# Relay_Control.net
KiCad netlist of a schematic drawn in Altium Designer
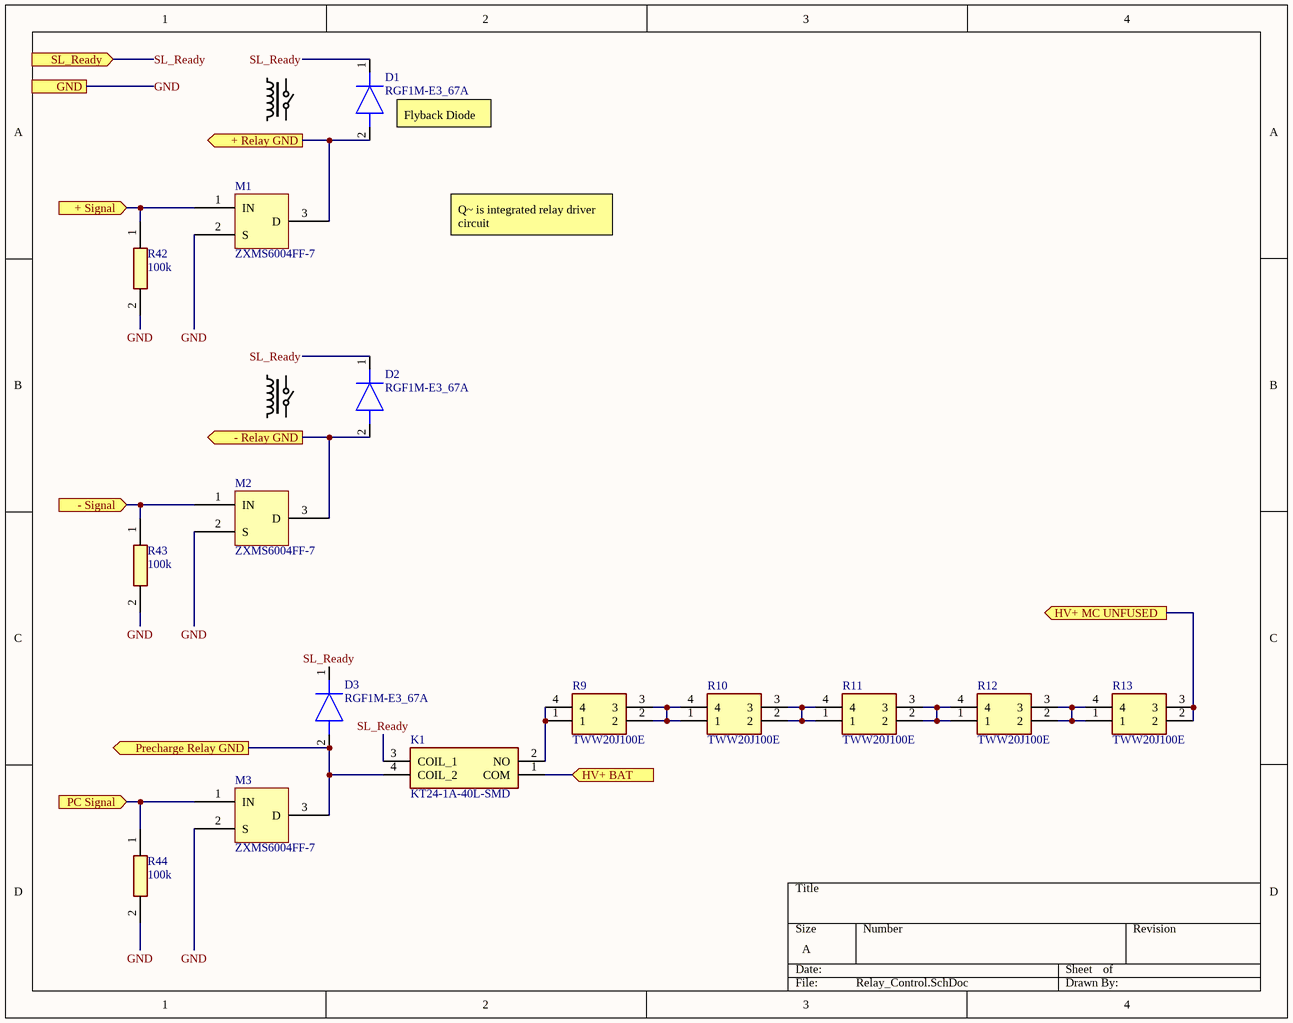
[diagram p0: Relay_Control.SchDoc]

(export (version "E")
  (design (tool "Eeschema 10.0.6"))
  (components
    (comp (ref "D1")
      (value "RGF1M-E3_67A")
      (footprint "SamacSys:DIOM5426X300N")
      (description "Diode")
      (fields
        (field (name "MANUFACTURER_PART_NUMBER") "RGF1M-E3/67A")
        (field (name "MOUSER PART NUMBER") "625-RGF1M-E3")
      )
      (libsource (lib "SamacSys") (part "RGF1M-E3_67A"))
    )
    (comp (ref "D2")
      (value "RGF1M-E3_67A")
      (footprint "SamacSys:DIOM5426X300N")
      (description "Diode")
      (fields
        (field (name "MANUFACTURER_PART_NUMBER") "RGF1M-E3/67A")
        (field (name "MOUSER PART NUMBER") "625-RGF1M-E3")
      )
      (libsource (lib "SamacSys") (part "RGF1M-E3_67A"))
    )
    (comp (ref "D3")
      (value "RGF1M-E3_67A")
      (footprint "SamacSys:DIOM5426X300N")
      (description "Diode")
      (fields
        (field (name "MANUFACTURER_PART_NUMBER") "RGF1M-E3/67A")
        (field (name "MOUSER PART NUMBER") "625-RGF1M-E3")
      )
      (libsource (lib "SamacSys") (part "RGF1M-E3_67A"))
    )
    (comp (ref "K1")
      (value "KT24-1A-40L-SMD")
      (footprint "SamacSys:KT241A40LSMD")
      (description "Relay or Contactor")
      (fields (field (name "MOUSER PART NUMBER") "876-KT24-1A-40L-SMD"))
      (libsource (lib "*") (part "KT24-1A-40L-SMD"))
    )
    (comp (ref "M1")
      (value "ZXMS6004FF-7")
      (footprint "SamacSys:SOT95P240X100-3N")
      (libsource (lib "SamacSys") (part "ZXMS6004FF-7"))
    )
    (comp (ref "M2")
      (value "ZXMS6004FF-7")
      (footprint "SamacSys:SOT95P240X100-3N")
      (libsource (lib "SamacSys") (part "ZXMS6004FF-7"))
    )
    (comp (ref "M3")
      (value "ZXMS6004FF-7")
      (footprint "SamacSys:SOT95P240X100-3N")
      (libsource (lib "SamacSys") (part "ZXMS6004FF-7"))
    )
    (comp (ref "R9")
      (value "TWW20J100E")
      (footprint "SamacSys:TWW20J100E")
      (description "Resistor")
      (fields (field (name "MOUSER PART NUMBER") "588-TWW20J100E"))
      (libsource (lib "*") (part "TWW20J100E"))
    )
    (comp (ref "R10")
      (value "TWW20J100E")
      (footprint "SamacSys:TWW20J100E")
      (description "Resistor")
      (fields (field (name "MOUSER PART NUMBER") "588-TWW20J100E"))
      (libsource (lib "*") (part "TWW20J100E"))
    )
    (comp (ref "R11")
      (value "TWW20J100E")
      (footprint "SamacSys:TWW20J100E")
      (description "Resistor")
      (fields (field (name "MOUSER PART NUMBER") "588-TWW20J100E"))
      (libsource (lib "*") (part "TWW20J100E"))
    )
    (comp (ref "R12")
      (value "TWW20J100E")
      (footprint "SamacSys:TWW20J100E")
      (description "Resistor")
      (fields (field (name "MOUSER PART NUMBER") "588-TWW20J100E"))
      (libsource (lib "*") (part "TWW20J100E"))
    )
    (comp (ref "R13")
      (value "TWW20J100E")
      (footprint "SamacSys:TWW20J100E")
      (description "Resistor")
      (fields (field (name "MOUSER PART NUMBER") "588-TWW20J100E"))
      (libsource (lib "*") (part "TWW20J100E"))
    )
    (comp (ref "R42")
      (value "100k")
      (footprint "SamacSys:RESC3216X65N")
      (description "Resistor")
      (fields (field (name "MANUFACTURER_PART_NUMBER") "MCA1206ME1003BP500"))
      (libsource (lib "*") (part "MCA1206ME1003BP500"))
    )
    (comp (ref "R43")
      (value "100k")
      (footprint "SamacSys:RESC3216X65N")
      (description "Resistor")
      (fields (field (name "MANUFACTURER_PART_NUMBER") "MCA1206ME1003BP500"))
      (libsource (lib "*") (part "MCA1206ME1003BP500"))
    )
    (comp (ref "R44")
      (value "100k")
      (footprint "SamacSys:RESC3216X65N")
      (description "Resistor")
      (fields (field (name "MANUFACTURER_PART_NUMBER") "MCA1206ME1003BP500"))
      (libsource (lib "*") (part "MCA1206ME1003BP500"))
    )
  )
  (nets
    (net (code "1") (name "/+ Relay GND") (class "Default")
      (node (ref "D1") (pin "2") (pinfunction "A_2") (pintype "passive"))
      (node (ref "M1") (pin "3") (pinfunction "D_3") (pintype "passive"))
    )
    (net (code "2") (name "/+ Signal") (class "Default")
      (node (ref "M1") (pin "1") (pinfunction "IN_1") (pintype "passive"))
      (node (ref "R42") (pin "1") (pinfunction "1_1") (pintype "passive"))
    )
    (net (code "3") (name "/- Relay GND") (class "Default")
      (node (ref "D2") (pin "2") (pinfunction "A_2") (pintype "passive"))
      (node (ref "M2") (pin "3") (pinfunction "D_3") (pintype "passive"))
    )
    (net (code "4") (name "/- Signal") (class "Default")
      (node (ref "M2") (pin "1") (pinfunction "IN_1") (pintype "passive"))
      (node (ref "R43") (pin "1") (pinfunction "1_1") (pintype "passive"))
    )
    (net (code "5") (name "/GND") (class "Default")
      (node (ref "M1") (pin "2") (pinfunction "S_2") (pintype "passive"))
      (node (ref "M2") (pin "2") (pinfunction "S_2") (pintype "passive"))
      (node (ref "M3") (pin "2") (pinfunction "S_2") (pintype "passive"))
      (node (ref "R42") (pin "2") (pinfunction "2_2") (pintype "passive"))
      (node (ref "R43") (pin "2") (pinfunction "2_2") (pintype "passive"))
      (node (ref "R44") (pin "2") (pinfunction "2_2") (pintype "passive"))
    )
    (net (code "6") (name "/HV+ BAT") (class "Default")
      (node (ref "K1") (pin "1") (pinfunction "COM_1") (pintype "passive"))
    )
    (net (code "7") (name "/HV+ MC UNFUSED") (class "Default")
      (node (ref "R13") (pin "2") (pinfunction "2_2") (pintype "passive"))
      (node (ref "R13") (pin "3") (pinfunction "3_3") (pintype "passive"))
    )
    (net (code "8") (name "/PC Signal") (class "Default")
      (node (ref "M3") (pin "1") (pinfunction "IN_1") (pintype "passive"))
      (node (ref "R44") (pin "1") (pinfunction "1_1") (pintype "passive"))
    )
    (net (code "9") (name "/Precharge Relay GND") (class "Default")
      (node (ref "D3") (pin "2") (pinfunction "A_2") (pintype "passive"))
      (node (ref "K1") (pin "4") (pinfunction "COIL_2_4") (pintype "passive"))
      (node (ref "M3") (pin "3") (pinfunction "D_3") (pintype "passive"))
    )
    (net (code "10") (name "/SL_Ready") (class "Default")
      (node (ref "D1") (pin "1") (pinfunction "K_1") (pintype "passive"))
      (node (ref "D2") (pin "1") (pinfunction "K_1") (pintype "passive"))
      (node (ref "D3") (pin "1") (pinfunction "K_1") (pintype "passive"))
      (node (ref "K1") (pin "3") (pinfunction "COIL_1_3") (pintype "passive"))
    )
    (net (code "11") (name "Net-(K1-NO)") (class "Default")
      (node (ref "K1") (pin "2") (pinfunction "NO_2") (pintype "passive"))
      (node (ref "R9") (pin "1") (pinfunction "1_1") (pintype "passive"))
      (node (ref "R9") (pin "4") (pinfunction "4_4") (pintype "passive"))
    )
    (net (code "12") (name "Net-(R10-Pad1)") (class "Default")
      (node (ref "R10") (pin "1") (pinfunction "1_1") (pintype "passive"))
      (node (ref "R10") (pin "4") (pinfunction "4_4") (pintype "passive"))
      (node (ref "R9") (pin "2") (pinfunction "2_2") (pintype "passive"))
      (node (ref "R9") (pin "3") (pinfunction "3_3") (pintype "passive"))
    )
    (net (code "13") (name "Net-(R10-Pad2)") (class "Default")
      (node (ref "R10") (pin "2") (pinfunction "2_2") (pintype "passive"))
      (node (ref "R10") (pin "3") (pinfunction "3_3") (pintype "passive"))
      (node (ref "R11") (pin "1") (pinfunction "1_1") (pintype "passive"))
      (node (ref "R11") (pin "4") (pinfunction "4_4") (pintype "passive"))
    )
    (net (code "14") (name "Net-(R11-Pad2)") (class "Default")
      (node (ref "R11") (pin "2") (pinfunction "2_2") (pintype "passive"))
      (node (ref "R11") (pin "3") (pinfunction "3_3") (pintype "passive"))
      (node (ref "R12") (pin "1") (pinfunction "1_1") (pintype "passive"))
      (node (ref "R12") (pin "4") (pinfunction "4_4") (pintype "passive"))
    )
    (net (code "15") (name "Net-(R12-Pad2)") (class "Default")
      (node (ref "R12") (pin "2") (pinfunction "2_2") (pintype "passive"))
      (node (ref "R12") (pin "3") (pinfunction "3_3") (pintype "passive"))
      (node (ref "R13") (pin "1") (pinfunction "1_1") (pintype "passive"))
      (node (ref "R13") (pin "4") (pinfunction "4_4") (pintype "passive"))
    )
  )
)
